# WalkerStalkerv3_0.net
KiCad netlist of a schematic drawn in EAGLE
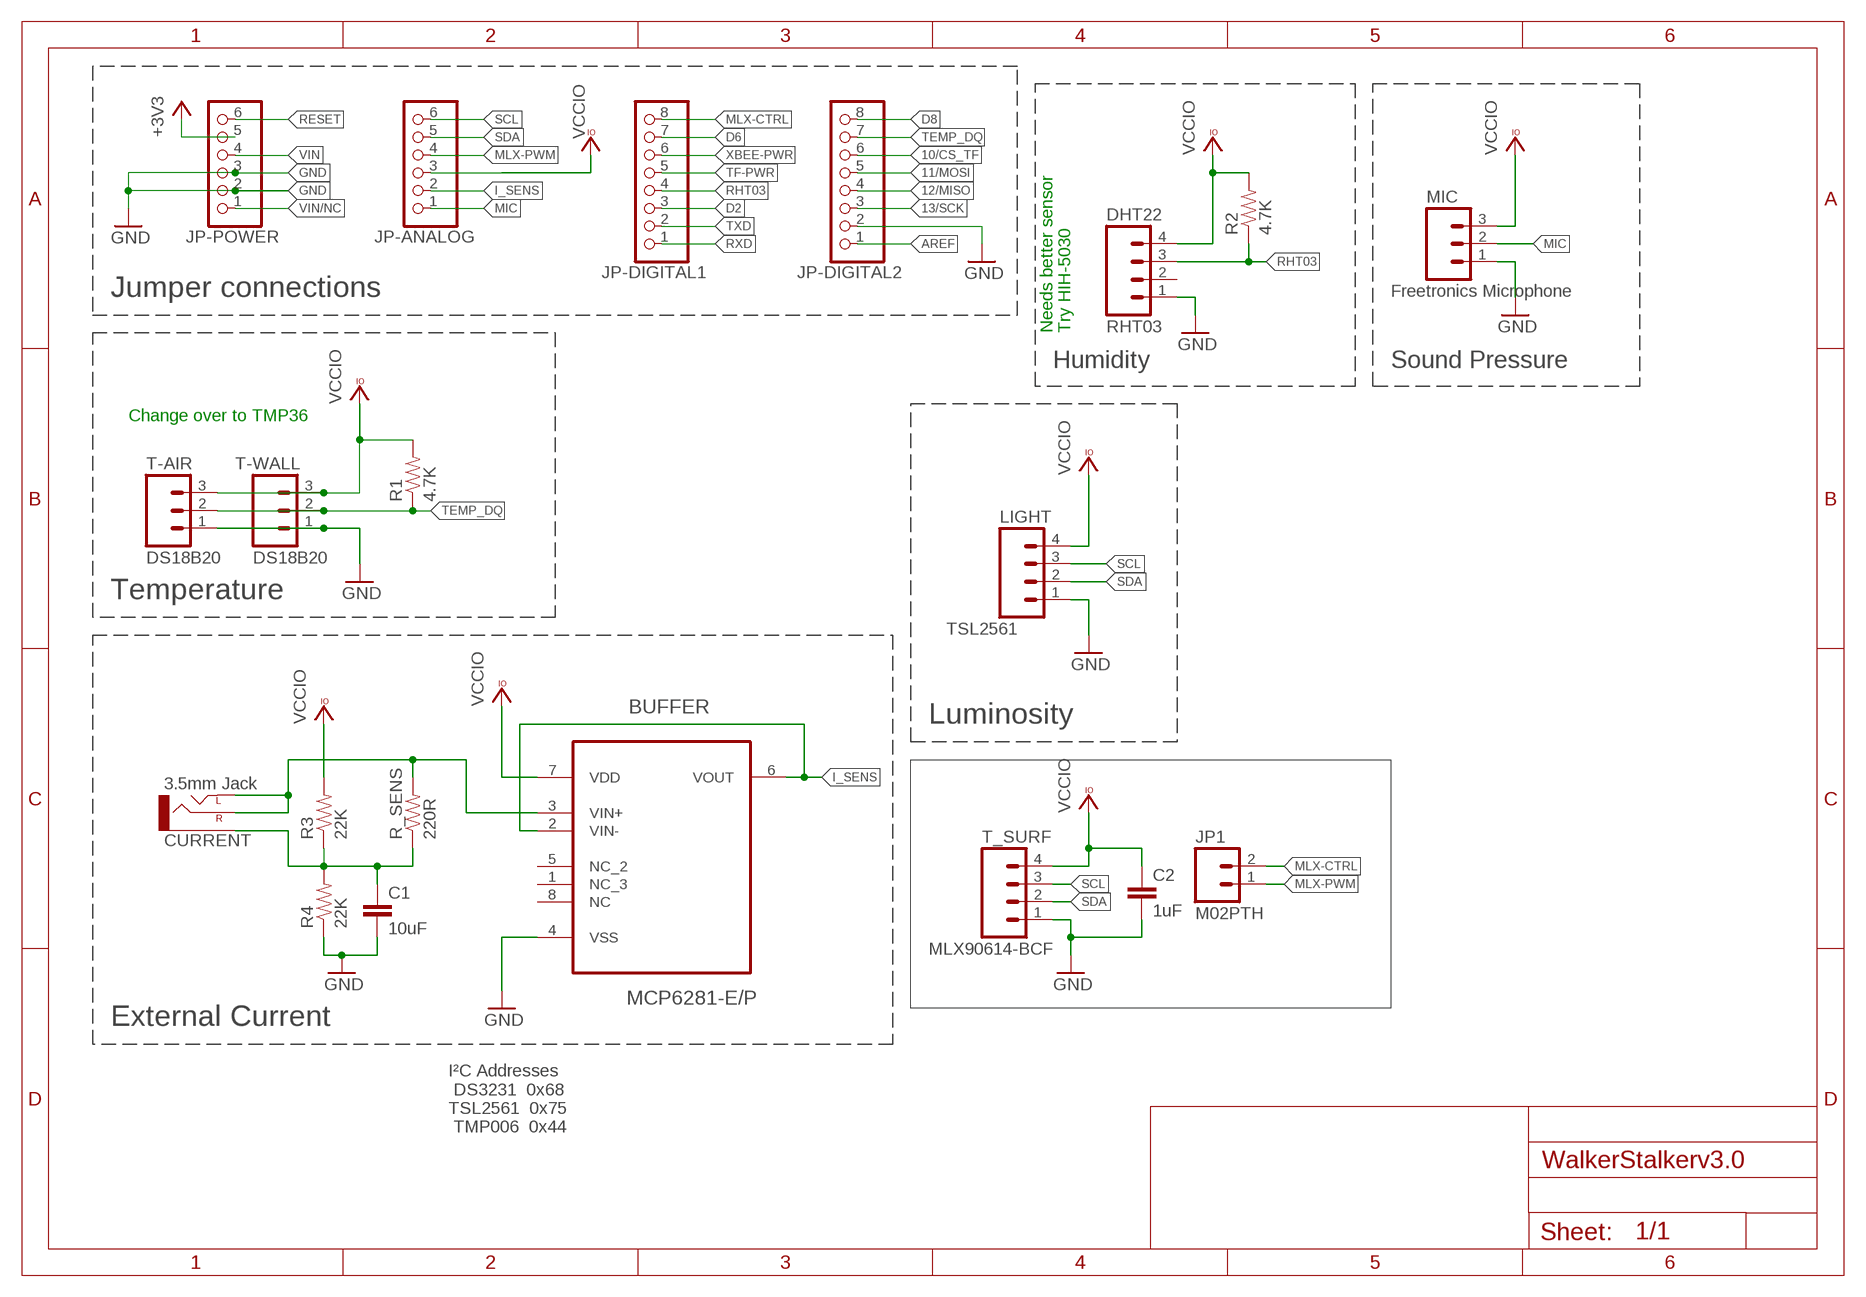
[diagram p0: schematic, sheet 1, part 1 of 2]
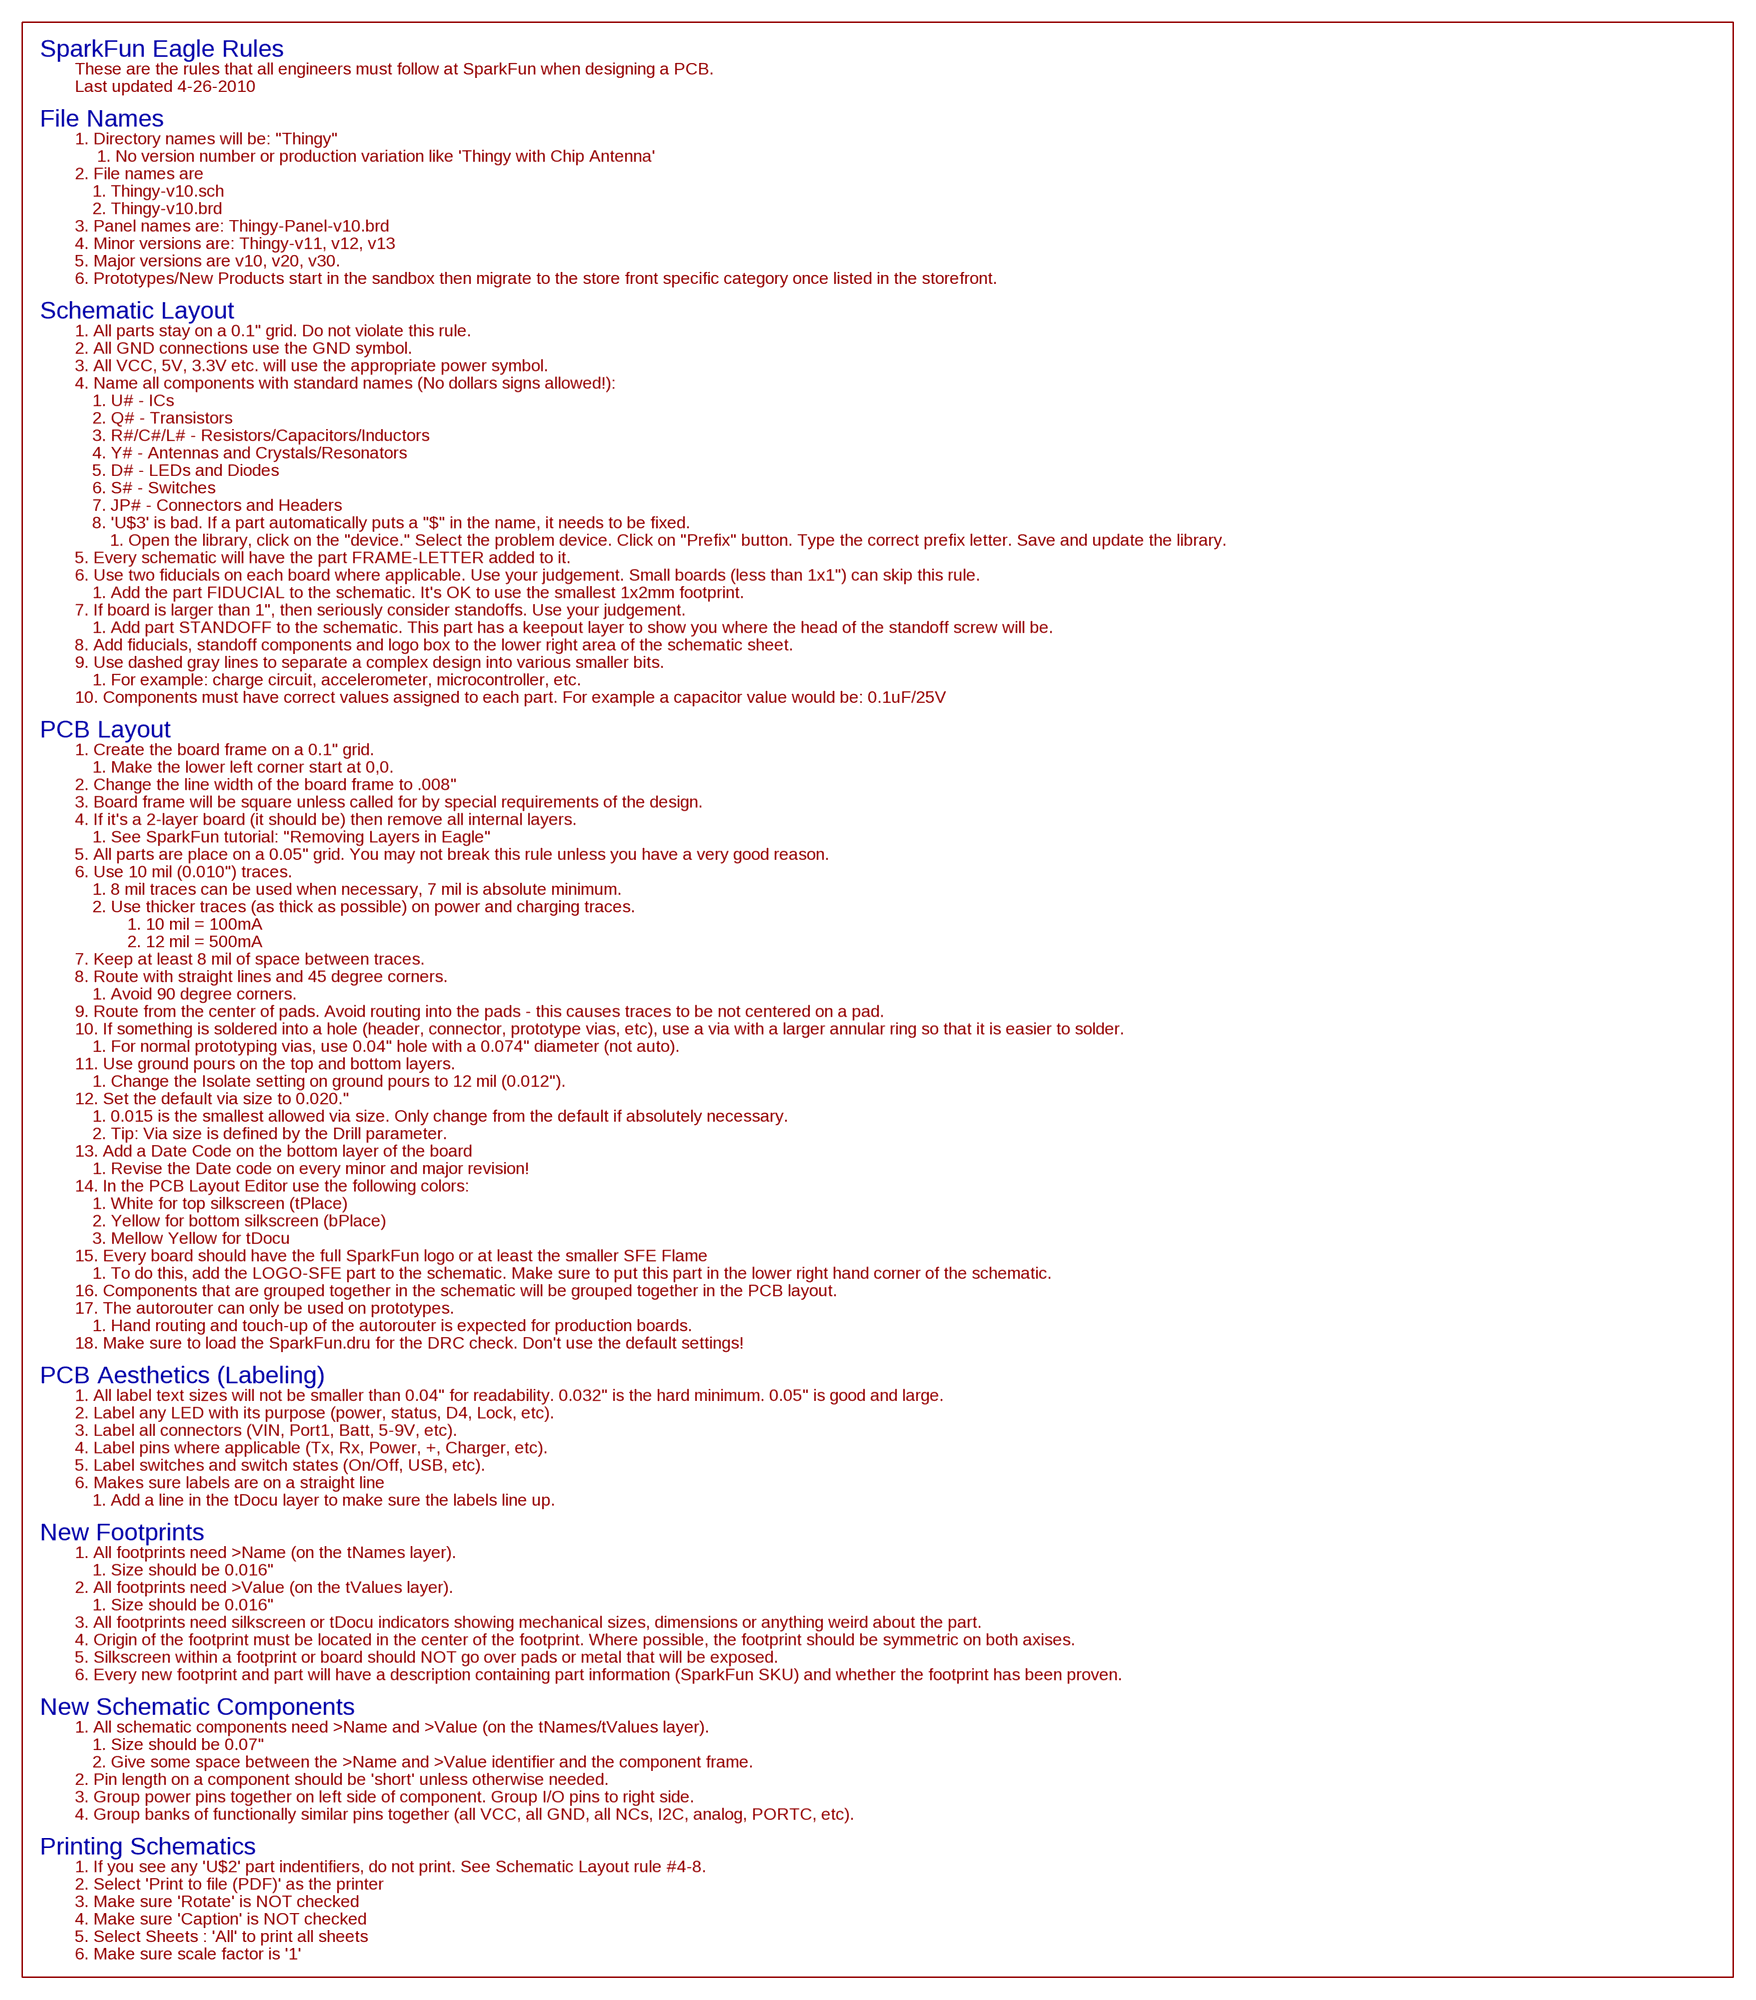
[diagram p1: schematic, sheet 1, part 2 of 2]

(export (version "E")
  (design (tool "Eeschema 10.0.6"))
  (components
    (comp (ref "BUFFER")
      (value "MCP6281-E/P")
      (footprint "eagle-import:DIP254P762X432-8")
      (libsource (lib "eagle-import") (part "MCP6281-E/P"))
    )
    (comp (ref "C1")
      (value "10uF")
      (footprint "eagle-import:1206")
      (libsource (lib "eagle-import") (part "CAP1206"))
    )
    (comp (ref "C2")
      (value "1uF")
      (footprint "eagle-import:1206")
      (libsource (lib "eagle-import") (part "CAP1206"))
    )
    (comp (ref "CURRENT")
      (value "3.5mm Jack")
      (footprint "eagle-import:AUDIO-JACK")
      (libsource (lib "eagle-import") (part "AUDIO-JACKPTH"))
    )
    (comp (ref "DHT22")
      (value "RHT03")
      (footprint "eagle-import:1X04")
      (libsource (lib "eagle-import") (part "M04PTH"))
    )
    (comp (ref "JP-ANALOG")
      (value "PINHD-1X6CB")
      (footprint "eagle-import:1X06-CLEANBIG")
      (libsource (lib "eagle-import") (part "PINHD-1X6CB"))
    )
    (comp (ref "JP-DIGITAL1")
      (value "PINHD-1X8CLEANBIG")
      (footprint "eagle-import:1X08-CLEANBIG")
      (libsource (lib "eagle-import") (part "PINHD-1X8CLEANBIG"))
    )
    (comp (ref "JP-DIGITAL2")
      (value "PINHD-1X8CLEANBIG")
      (footprint "eagle-import:1X08-CLEANBIG")
      (libsource (lib "eagle-import") (part "PINHD-1X8CLEANBIG"))
    )
    (comp (ref "JP-POWER")
      (value "PINHD-1X6CB")
      (footprint "eagle-import:1X06-CLEANBIG")
      (libsource (lib "eagle-import") (part "PINHD-1X6CB"))
    )
    (comp (ref "JP1")
      (value "M02PTH")
      (footprint "eagle-import:1X02")
      (libsource (lib "eagle-import") (part "M02PTH"))
    )
    (comp (ref "LIGHT")
      (value "TSL2561")
      (footprint "eagle-import:1X04")
      (libsource (lib "eagle-import") (part "M04PTH"))
    )
    (comp (ref "MIC")
      (value "Freetronics Microphone")
      (footprint "eagle-import:1X03")
      (libsource (lib "eagle-import") (part "M03PTH"))
    )
    (comp (ref "R1")
      (value "4.7K")
      (footprint "eagle-import:1206")
      (libsource (lib "eagle-import") (part "RESISTOR1206"))
    )
    (comp (ref "R2")
      (value "4.7K")
      (footprint "eagle-import:1206")
      (libsource (lib "eagle-import") (part "RESISTOR1206"))
    )
    (comp (ref "R3")
      (value "22K")
      (footprint "eagle-import:1206")
      (libsource (lib "eagle-import") (part "RESISTOR1206"))
    )
    (comp (ref "R4")
      (value "22K")
      (footprint "eagle-import:1206")
      (libsource (lib "eagle-import") (part "RESISTOR1206"))
    )
    (comp (ref "R_SENS")
      (value "220R")
      (footprint "eagle-import:1206")
      (libsource (lib "eagle-import") (part "RESISTOR1206"))
    )
    (comp (ref "T-AIR")
      (value "DS18B20")
      (footprint "eagle-import:1X03")
      (libsource (lib "eagle-import") (part "M03PTH"))
    )
    (comp (ref "T-WALL")
      (value "DS18B20")
      (footprint "eagle-import:1X03")
      (libsource (lib "eagle-import") (part "M03PTH"))
    )
    (comp (ref "T_SURF")
      (value "MLX90614-BCF")
      (footprint "eagle-import:1X04")
      (libsource (lib "eagle-import") (part "M04PTH"))
    )
  )
  (nets
    (net (code "1") (name "+3V3") (class "Default")
      (node (ref "JP-POWER") (pin "5") (pinfunction "5_5") (pintype "passive"))
    )
    (net (code "2") (name "10{slash}CS_TF") (class "Default")
      (node (ref "JP-DIGITAL2") (pin "6") (pinfunction "6_6") (pintype "passive"))
    )
    (net (code "3") (name "11{slash}MOSI") (class "Default")
      (node (ref "JP-DIGITAL2") (pin "5") (pinfunction "5_5") (pintype "passive"))
    )
    (net (code "4") (name "12{slash}MISO") (class "Default")
      (node (ref "JP-DIGITAL2") (pin "4") (pinfunction "4_4") (pintype "passive"))
    )
    (net (code "5") (name "13{slash}SCK") (class "Default")
      (node (ref "JP-DIGITAL2") (pin "3") (pinfunction "3_3") (pintype "passive"))
    )
    (net (code "6") (name "AREF") (class "Default")
      (node (ref "JP-DIGITAL2") (pin "1") (pinfunction "1_1") (pintype "passive"))
    )
    (net (code "7") (name "D2") (class "Default")
      (node (ref "JP-DIGITAL1") (pin "3") (pinfunction "3_3") (pintype "passive"))
    )
    (net (code "8") (name "D6") (class "Default")
      (node (ref "JP-DIGITAL1") (pin "7") (pinfunction "7_7") (pintype "passive"))
    )
    (net (code "9") (name "D8") (class "Default")
      (node (ref "JP-DIGITAL2") (pin "8") (pinfunction "8_8") (pintype "passive"))
    )
    (net (code "10") (name "GND") (class "Default")
      (node (ref "BUFFER") (pin "4") (pinfunction "VSS_4") (pintype "power_in"))
      (node (ref "C1") (pin "2") (pinfunction "2_2") (pintype "passive"))
      (node (ref "C2") (pin "2") (pinfunction "2_2") (pintype "passive"))
      (node (ref "DHT22") (pin "1") (pinfunction "1_1") (pintype "passive"))
      (node (ref "JP-DIGITAL2") (pin "2") (pinfunction "2_2") (pintype "passive"))
      (node (ref "JP-POWER") (pin "2") (pinfunction "2_2") (pintype "passive"))
      (node (ref "JP-POWER") (pin "3") (pinfunction "3_3") (pintype "passive"))
      (node (ref "LIGHT") (pin "1") (pinfunction "1_1") (pintype "passive"))
      (node (ref "MIC") (pin "1") (pinfunction "1_1") (pintype "passive"))
      (node (ref "R4") (pin "1") (pinfunction "1_1") (pintype "passive"))
      (node (ref "T-AIR") (pin "1") (pinfunction "1_1") (pintype "passive"))
      (node (ref "T-WALL") (pin "1") (pinfunction "1_1") (pintype "passive"))
      (node (ref "T_SURF") (pin "1") (pinfunction "1_1") (pintype "passive"))
    )
    (net (code "11") (name "I_SENS") (class "Default")
      (node (ref "BUFFER") (pin "2") (pinfunction "VIN-_2") (pintype "input"))
      (node (ref "BUFFER") (pin "6") (pinfunction "VOUT_6") (pintype "output"))
      (node (ref "JP-ANALOG") (pin "2") (pinfunction "2_2") (pintype "passive"))
    )
    (net (code "12") (name "MIC") (class "Default")
      (node (ref "JP-ANALOG") (pin "1") (pinfunction "1_1") (pintype "passive"))
      (node (ref "MIC") (pin "2") (pinfunction "2_2") (pintype "passive"))
    )
    (net (code "13") (name "MLX-CTRL") (class "Default")
      (node (ref "JP-DIGITAL1") (pin "8") (pinfunction "8_8") (pintype "passive"))
      (node (ref "JP1") (pin "2") (pinfunction "2_2") (pintype "passive"))
    )
    (net (code "14") (name "MLX-PWM") (class "Default")
      (node (ref "JP-ANALOG") (pin "4") (pinfunction "4_4") (pintype "passive"))
      (node (ref "JP1") (pin "1") (pinfunction "1_1") (pintype "passive"))
    )
    (net (code "15") (name "Net-(BUFFER-VIN+)") (class "Default")
      (node (ref "BUFFER") (pin "3") (pinfunction "VIN+_3") (pintype "input"))
      (node (ref "CURRENT") (pin "RING") (pinfunction "RIGHT_RING") (pintype "bidirectional"))
      (node (ref "CURRENT") (pin "TIP") (pinfunction "LEFT_TIP") (pintype "bidirectional"))
      (node (ref "R_SENS") (pin "2") (pinfunction "2_2") (pintype "passive"))
    )
    (net (code "16") (name "Net-(C1-Pad1)") (class "Default")
      (node (ref "C1") (pin "1") (pinfunction "1_1") (pintype "passive"))
      (node (ref "CURRENT") (pin "SLEEVE") (pinfunction "SLEEVE_SLEEVE") (pintype "bidirectional"))
      (node (ref "R3") (pin "1") (pinfunction "1_1") (pintype "passive"))
      (node (ref "R4") (pin "2") (pinfunction "2_2") (pintype "passive"))
      (node (ref "R_SENS") (pin "1") (pinfunction "1_1") (pintype "passive"))
    )
    (net (code "17") (name "RESET") (class "Default")
      (node (ref "JP-POWER") (pin "6") (pinfunction "6_6") (pintype "passive"))
    )
    (net (code "18") (name "RHT03") (class "Default")
      (node (ref "DHT22") (pin "3") (pinfunction "3_3") (pintype "passive"))
      (node (ref "JP-DIGITAL1") (pin "4") (pinfunction "4_4") (pintype "passive"))
      (node (ref "R2") (pin "1") (pinfunction "1_1") (pintype "passive"))
    )
    (net (code "19") (name "RXD") (class "Default")
      (node (ref "JP-DIGITAL1") (pin "1") (pinfunction "1_1") (pintype "passive"))
    )
    (net (code "20") (name "SCL") (class "Default")
      (node (ref "JP-ANALOG") (pin "6") (pinfunction "6_6") (pintype "passive"))
      (node (ref "LIGHT") (pin "3") (pinfunction "3_3") (pintype "passive"))
      (node (ref "T_SURF") (pin "3") (pinfunction "3_3") (pintype "passive"))
    )
    (net (code "21") (name "SDA") (class "Default")
      (node (ref "JP-ANALOG") (pin "5") (pinfunction "5_5") (pintype "passive"))
      (node (ref "LIGHT") (pin "2") (pinfunction "2_2") (pintype "passive"))
      (node (ref "T_SURF") (pin "2") (pinfunction "2_2") (pintype "passive"))
    )
    (net (code "22") (name "TEMP_DQ") (class "Default")
      (node (ref "JP-DIGITAL2") (pin "7") (pinfunction "7_7") (pintype "passive"))
      (node (ref "R1") (pin "1") (pinfunction "1_1") (pintype "passive"))
      (node (ref "T-AIR") (pin "2") (pinfunction "2_2") (pintype "passive"))
      (node (ref "T-WALL") (pin "2") (pinfunction "2_2") (pintype "passive"))
    )
    (net (code "23") (name "TF-PWR") (class "Default")
      (node (ref "JP-DIGITAL1") (pin "5") (pinfunction "5_5") (pintype "passive"))
    )
    (net (code "24") (name "TXD") (class "Default")
      (node (ref "JP-DIGITAL1") (pin "2") (pinfunction "2_2") (pintype "passive"))
    )
    (net (code "25") (name "VCCIO") (class "Default")
      (node (ref "BUFFER") (pin "7") (pinfunction "VDD_7") (pintype "power_in"))
      (node (ref "C2") (pin "1") (pinfunction "1_1") (pintype "passive"))
      (node (ref "DHT22") (pin "4") (pinfunction "4_4") (pintype "passive"))
      (node (ref "JP-ANALOG") (pin "3") (pinfunction "3_3") (pintype "passive"))
      (node (ref "LIGHT") (pin "4") (pinfunction "4_4") (pintype "passive"))
      (node (ref "MIC") (pin "3") (pinfunction "3_3") (pintype "passive"))
      (node (ref "R1") (pin "2") (pinfunction "2_2") (pintype "passive"))
      (node (ref "R2") (pin "2") (pinfunction "2_2") (pintype "passive"))
      (node (ref "R3") (pin "2") (pinfunction "2_2") (pintype "passive"))
      (node (ref "T-AIR") (pin "3") (pinfunction "3_3") (pintype "passive"))
      (node (ref "T-WALL") (pin "3") (pinfunction "3_3") (pintype "passive"))
      (node (ref "T_SURF") (pin "4") (pinfunction "4_4") (pintype "passive"))
    )
    (net (code "26") (name "VIN") (class "Default")
      (node (ref "JP-POWER") (pin "4") (pinfunction "4_4") (pintype "passive"))
    )
    (net (code "27") (name "VIN{slash}NC") (class "Default")
      (node (ref "JP-POWER") (pin "1") (pinfunction "1_1") (pintype "passive"))
    )
    (net (code "28") (name "XBEE-PWR") (class "Default")
      (node (ref "JP-DIGITAL1") (pin "6") (pinfunction "6_6") (pintype "passive"))
    )
    (net (code "29") (name "unconnected-(BUFFER-NC-Pad8)") (class "Default")
      (node (ref "BUFFER") (pin "8") (pinfunction "NC_8") (pintype "no_connect"))
    )
    (net (code "30") (name "unconnected-(BUFFER-NC_2-Pad5)") (class "Default")
      (node (ref "BUFFER") (pin "5") (pinfunction "NC_2_5") (pintype "no_connect"))
    )
    (net (code "31") (name "unconnected-(BUFFER-NC_3-Pad1)") (class "Default")
      (node (ref "BUFFER") (pin "1") (pinfunction "NC_3_1") (pintype "no_connect"))
    )
    (net (code "32") (name "unconnected-(DHT22-Pad2)") (class "Default")
      (node (ref "DHT22") (pin "2") (pinfunction "2_2") (pintype "passive"))
    )
  )
)
